# 09-09e.net
KiCad netlist of a schematic drawn in EAGLE
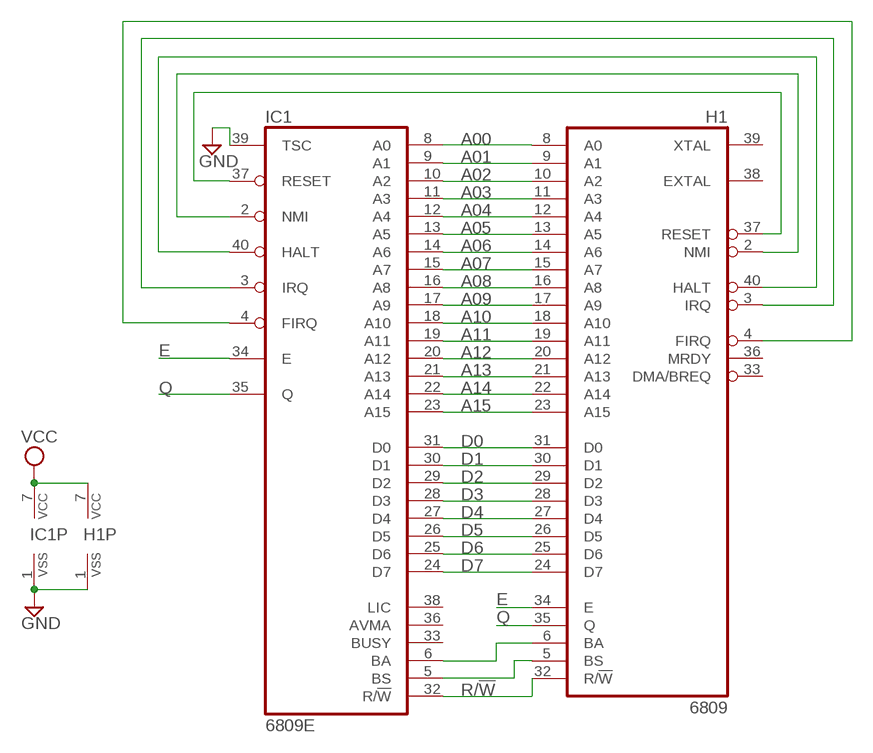
[diagram p0: schematic, sheet 1]
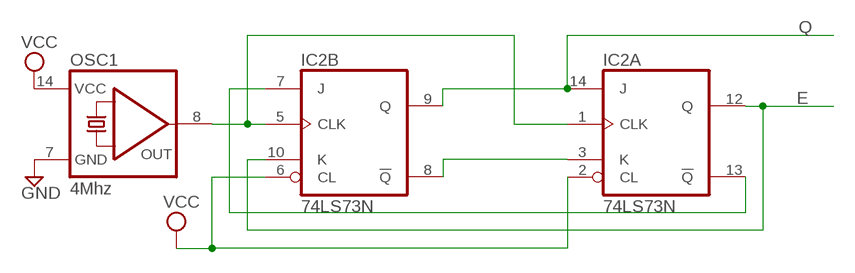
[diagram p1: schematic, sheet 2]

(export (version "E")
  (design (tool "Eeschema 10.0.6"))
  (components
    (comp (ref "IC2")
      (value "74LS73N")
      (footprint "eagle-import:DIL14")
      (libsource (lib "eagle-import") (part "7473NLS"))
    )
    (comp (ref "OSC1")
      (value "4Mhz")
      (footprint "eagle-import:DIL14S")
      (libsource (lib "eagle-import") (part "QG5860"))
    )
    (comp (ref "H1")
      (value "6809")
      (footprint "eagle-import:DIL40")
      (fields (field (name "MF") "NTE ELECTRONICS") (field (name "MPN") "NTE6809"))
      (libsource (lib "eagle-import") (part "6809"))
    )
    (comp (ref "IC1")
      (value "6809E")
      (footprint "eagle-import:DIL40")
      (fields (field (name "MF") "NTE ELECTRONICS") (field (name "MPN") "NTE6809E"))
      (libsource (lib "eagle-import") (part "6809E"))
    )
  )
  (nets
    (net (code "1") (name "A00") (class "Default")
      (node (ref "H1") (pin "8") (pinfunction "A0_8") (pintype "tri_state"))
      (node (ref "IC1") (pin "8") (pinfunction "A0_8") (pintype "tri_state"))
    )
    (net (code "2") (name "A01") (class "Default")
      (node (ref "H1") (pin "9") (pinfunction "A1_9") (pintype "tri_state"))
      (node (ref "IC1") (pin "9") (pinfunction "A1_9") (pintype "tri_state"))
    )
    (net (code "3") (name "A02") (class "Default")
      (node (ref "H1") (pin "10") (pinfunction "A2_10") (pintype "tri_state"))
      (node (ref "IC1") (pin "10") (pinfunction "A2_10") (pintype "tri_state"))
    )
    (net (code "4") (name "A03") (class "Default")
      (node (ref "H1") (pin "11") (pinfunction "A3_11") (pintype "tri_state"))
      (node (ref "IC1") (pin "11") (pinfunction "A3_11") (pintype "tri_state"))
    )
    (net (code "5") (name "A04") (class "Default")
      (node (ref "H1") (pin "12") (pinfunction "A4_12") (pintype "tri_state"))
      (node (ref "IC1") (pin "12") (pinfunction "A4_12") (pintype "tri_state"))
    )
    (net (code "6") (name "A05") (class "Default")
      (node (ref "H1") (pin "13") (pinfunction "A5_13") (pintype "tri_state"))
      (node (ref "IC1") (pin "13") (pinfunction "A5_13") (pintype "tri_state"))
    )
    (net (code "7") (name "A06") (class "Default")
      (node (ref "H1") (pin "14") (pinfunction "A6_14") (pintype "tri_state"))
      (node (ref "IC1") (pin "14") (pinfunction "A6_14") (pintype "tri_state"))
    )
    (net (code "8") (name "A07") (class "Default")
      (node (ref "H1") (pin "15") (pinfunction "A7_15") (pintype "tri_state"))
      (node (ref "IC1") (pin "15") (pinfunction "A7_15") (pintype "tri_state"))
    )
    (net (code "9") (name "A08") (class "Default")
      (node (ref "H1") (pin "16") (pinfunction "A8_16") (pintype "tri_state"))
      (node (ref "IC1") (pin "16") (pinfunction "A8_16") (pintype "tri_state"))
    )
    (net (code "10") (name "A09") (class "Default")
      (node (ref "H1") (pin "17") (pinfunction "A9_17") (pintype "tri_state"))
      (node (ref "IC1") (pin "17") (pinfunction "A9_17") (pintype "tri_state"))
    )
    (net (code "11") (name "A10") (class "Default")
      (node (ref "H1") (pin "18") (pinfunction "A10_18") (pintype "tri_state"))
      (node (ref "IC1") (pin "18") (pinfunction "A10_18") (pintype "tri_state"))
    )
    (net (code "12") (name "A11") (class "Default")
      (node (ref "H1") (pin "19") (pinfunction "A11_19") (pintype "tri_state"))
      (node (ref "IC1") (pin "19") (pinfunction "A11_19") (pintype "tri_state"))
    )
    (net (code "13") (name "A12") (class "Default")
      (node (ref "H1") (pin "20") (pinfunction "A12_20") (pintype "tri_state"))
      (node (ref "IC1") (pin "20") (pinfunction "A12_20") (pintype "tri_state"))
    )
    (net (code "14") (name "A13") (class "Default")
      (node (ref "H1") (pin "21") (pinfunction "A13_21") (pintype "tri_state"))
      (node (ref "IC1") (pin "21") (pinfunction "A13_21") (pintype "tri_state"))
    )
    (net (code "15") (name "A14") (class "Default")
      (node (ref "H1") (pin "22") (pinfunction "A14_22") (pintype "tri_state"))
      (node (ref "IC1") (pin "22") (pinfunction "A14_22") (pintype "tri_state"))
    )
    (net (code "16") (name "A15") (class "Default")
      (node (ref "H1") (pin "23") (pinfunction "A15_23") (pintype "tri_state"))
      (node (ref "IC1") (pin "23") (pinfunction "A15_23") (pintype "tri_state"))
    )
    (net (code "17") (name "D0") (class "Default")
      (node (ref "H1") (pin "31") (pinfunction "D0_31") (pintype "bidirectional"))
      (node (ref "IC1") (pin "31") (pinfunction "D0_31") (pintype "bidirectional"))
    )
    (net (code "18") (name "D1") (class "Default")
      (node (ref "H1") (pin "30") (pinfunction "D1_30") (pintype "bidirectional"))
      (node (ref "IC1") (pin "30") (pinfunction "D1_30") (pintype "bidirectional"))
    )
    (net (code "19") (name "D2") (class "Default")
      (node (ref "H1") (pin "29") (pinfunction "D2_29") (pintype "bidirectional"))
      (node (ref "IC1") (pin "29") (pinfunction "D2_29") (pintype "bidirectional"))
    )
    (net (code "20") (name "D3") (class "Default")
      (node (ref "H1") (pin "28") (pinfunction "D3_28") (pintype "bidirectional"))
      (node (ref "IC1") (pin "28") (pinfunction "D3_28") (pintype "bidirectional"))
    )
    (net (code "21") (name "D4") (class "Default")
      (node (ref "H1") (pin "27") (pinfunction "D4_27") (pintype "bidirectional"))
      (node (ref "IC1") (pin "27") (pinfunction "D4_27") (pintype "bidirectional"))
    )
    (net (code "22") (name "D5") (class "Default")
      (node (ref "H1") (pin "26") (pinfunction "D5_26") (pintype "bidirectional"))
      (node (ref "IC1") (pin "26") (pinfunction "D5_26") (pintype "bidirectional"))
    )
    (net (code "23") (name "D6") (class "Default")
      (node (ref "H1") (pin "25") (pinfunction "D6_25") (pintype "bidirectional"))
      (node (ref "IC1") (pin "25") (pinfunction "D6_25") (pintype "bidirectional"))
    )
    (net (code "24") (name "D7") (class "Default")
      (node (ref "H1") (pin "24") (pinfunction "D7_24") (pintype "bidirectional"))
      (node (ref "IC1") (pin "24") (pinfunction "D7_24") (pintype "bidirectional"))
    )
    (net (code "25") (name "E") (class "Default")
      (node (ref "H1") (pin "34") (pinfunction "E_34") (pintype "output"))
      (node (ref "IC1") (pin "34") (pinfunction "E_34") (pintype "input"))
      (node (ref "IC2") (pin "10") (pinfunction "K_10") (pintype "input"))
      (node (ref "IC2") (pin "12") (pinfunction "Q_12") (pintype "output"))
    )
    (net (code "26") (name "GND") (class "Default")
      (node (ref "H1") (pin "1") (pinfunction "VSS_1") (pintype "power_in"))
      (node (ref "IC1") (pin "1") (pinfunction "VSS_1") (pintype "power_in"))
      (node (ref "IC1") (pin "39") (pinfunction "TSC_39") (pintype "input"))
      (node (ref "OSC1") (pin "7") (pinfunction "GND_7") (pintype "power_in"))
    )
    (net (code "27") (name "Net-(H1A-BA)") (class "Default")
      (node (ref "H1") (pin "6") (pinfunction "BA_6") (pintype "output"))
      (node (ref "IC1") (pin "6") (pinfunction "BA_6") (pintype "output"))
    )
    (net (code "28") (name "Net-(H1A-BS)") (class "Default")
      (node (ref "H1") (pin "5") (pinfunction "BS_5") (pintype "output"))
      (node (ref "IC1") (pin "5") (pinfunction "BS_5") (pintype "output"))
    )
    (net (code "29") (name "Net-(H1A-FIRQ)") (class "Default")
      (node (ref "H1") (pin "4") (pinfunction "FIRQ_4") (pintype "input"))
      (node (ref "IC1") (pin "4") (pinfunction "FIRQ_4") (pintype "input"))
    )
    (net (code "30") (name "Net-(H1A-HALT)") (class "Default")
      (node (ref "H1") (pin "40") (pinfunction "HALT_40") (pintype "input"))
      (node (ref "IC1") (pin "40") (pinfunction "HALT_40") (pintype "input"))
    )
    (net (code "31") (name "Net-(H1A-IRQ)") (class "Default")
      (node (ref "H1") (pin "3") (pinfunction "IRQ_3") (pintype "input"))
      (node (ref "IC1") (pin "3") (pinfunction "IRQ_3") (pintype "input"))
    )
    (net (code "32") (name "Net-(H1A-NMI)") (class "Default")
      (node (ref "H1") (pin "2") (pinfunction "NMI_2") (pintype "input"))
      (node (ref "IC1") (pin "2") (pinfunction "NMI_2") (pintype "input"))
    )
    (net (code "33") (name "Net-(H1A-RESET)") (class "Default")
      (node (ref "H1") (pin "37") (pinfunction "RESET_37") (pintype "input"))
      (node (ref "IC1") (pin "37") (pinfunction "RESET_37") (pintype "input"))
    )
    (net (code "34") (name "Net-(IC2A-CLK)") (class "Default")
      (node (ref "IC2") (pin "1") (pinfunction "CLK_1") (pintype "input"))
      (node (ref "IC2") (pin "5") (pinfunction "CLK_5") (pintype "input"))
      (node (ref "OSC1") (pin "8") (pinfunction "OUT_8") (pintype "output"))
    )
    (net (code "35") (name "Net-(IC2A-K)") (class "Default")
      (node (ref "IC2") (pin "3") (pinfunction "K_3") (pintype "input"))
      (node (ref "IC2") (pin "8") (pinfunction "~{Q}_8") (pintype "output"))
    )
    (net (code "36") (name "Net-(IC2A-~{Q})") (class "Default")
      (node (ref "IC2") (pin "13") (pinfunction "~{Q}_13") (pintype "output"))
      (node (ref "IC2") (pin "7") (pinfunction "J_7") (pintype "input"))
    )
    (net (code "37") (name "Q") (class "Default")
      (node (ref "H1") (pin "35") (pinfunction "Q_35") (pintype "output"))
      (node (ref "IC1") (pin "35") (pinfunction "Q_35") (pintype "input"))
      (node (ref "IC2") (pin "14") (pinfunction "J_14") (pintype "input"))
      (node (ref "IC2") (pin "9") (pinfunction "Q_9") (pintype "output"))
    )
    (net (code "38") (name "R{slash}~{W}") (class "Default")
      (node (ref "H1") (pin "32") (pinfunction "R/~{W}_32") (pintype "output"))
      (node (ref "IC1") (pin "32") (pinfunction "R/~{W}_32") (pintype "output"))
    )
    (net (code "39") (name "VCC") (class "Default")
      (node (ref "H1") (pin "7") (pinfunction "VCC_7") (pintype "power_in"))
      (node (ref "IC1") (pin "7") (pinfunction "VCC_7") (pintype "power_in"))
      (node (ref "IC2") (pin "2") (pinfunction "CL_2") (pintype "input"))
      (node (ref "IC2") (pin "6") (pinfunction "CL_6") (pintype "input"))
      (node (ref "OSC1") (pin "14") (pinfunction "VCC_14") (pintype "power_in"))
    )
    (net (code "40") (name "unconnected-(H1A-DMA{slash}BREQ-Pad33)") (class "Default")
      (node (ref "H1") (pin "33") (pinfunction "DMA/BREQ_33") (pintype "input"))
    )
    (net (code "41") (name "unconnected-(H1A-EXTAL-Pad38)") (class "Default")
      (node (ref "H1") (pin "38") (pinfunction "EXTAL_38") (pintype "input"))
    )
    (net (code "42") (name "unconnected-(H1A-MRDY-Pad36)") (class "Default")
      (node (ref "H1") (pin "36") (pinfunction "MRDY_36") (pintype "input"))
    )
    (net (code "43") (name "unconnected-(H1A-XTAL-Pad39)") (class "Default")
      (node (ref "H1") (pin "39") (pinfunction "XTAL_39") (pintype "input"))
    )
    (net (code "44") (name "unconnected-(IC1A-AVMA-Pad36)") (class "Default")
      (node (ref "IC1") (pin "36") (pinfunction "AVMA_36") (pintype "output"))
    )
    (net (code "45") (name "unconnected-(IC1A-BUSY-Pad33)") (class "Default")
      (node (ref "IC1") (pin "33") (pinfunction "BUSY_33") (pintype "output"))
    )
    (net (code "46") (name "unconnected-(IC1A-LIC-Pad38)") (class "Default")
      (node (ref "IC1") (pin "38") (pinfunction "LIC_38") (pintype "output"))
    )
  )
)
